# Misc.net
KiCad netlist of a schematic drawn in Altium Designer
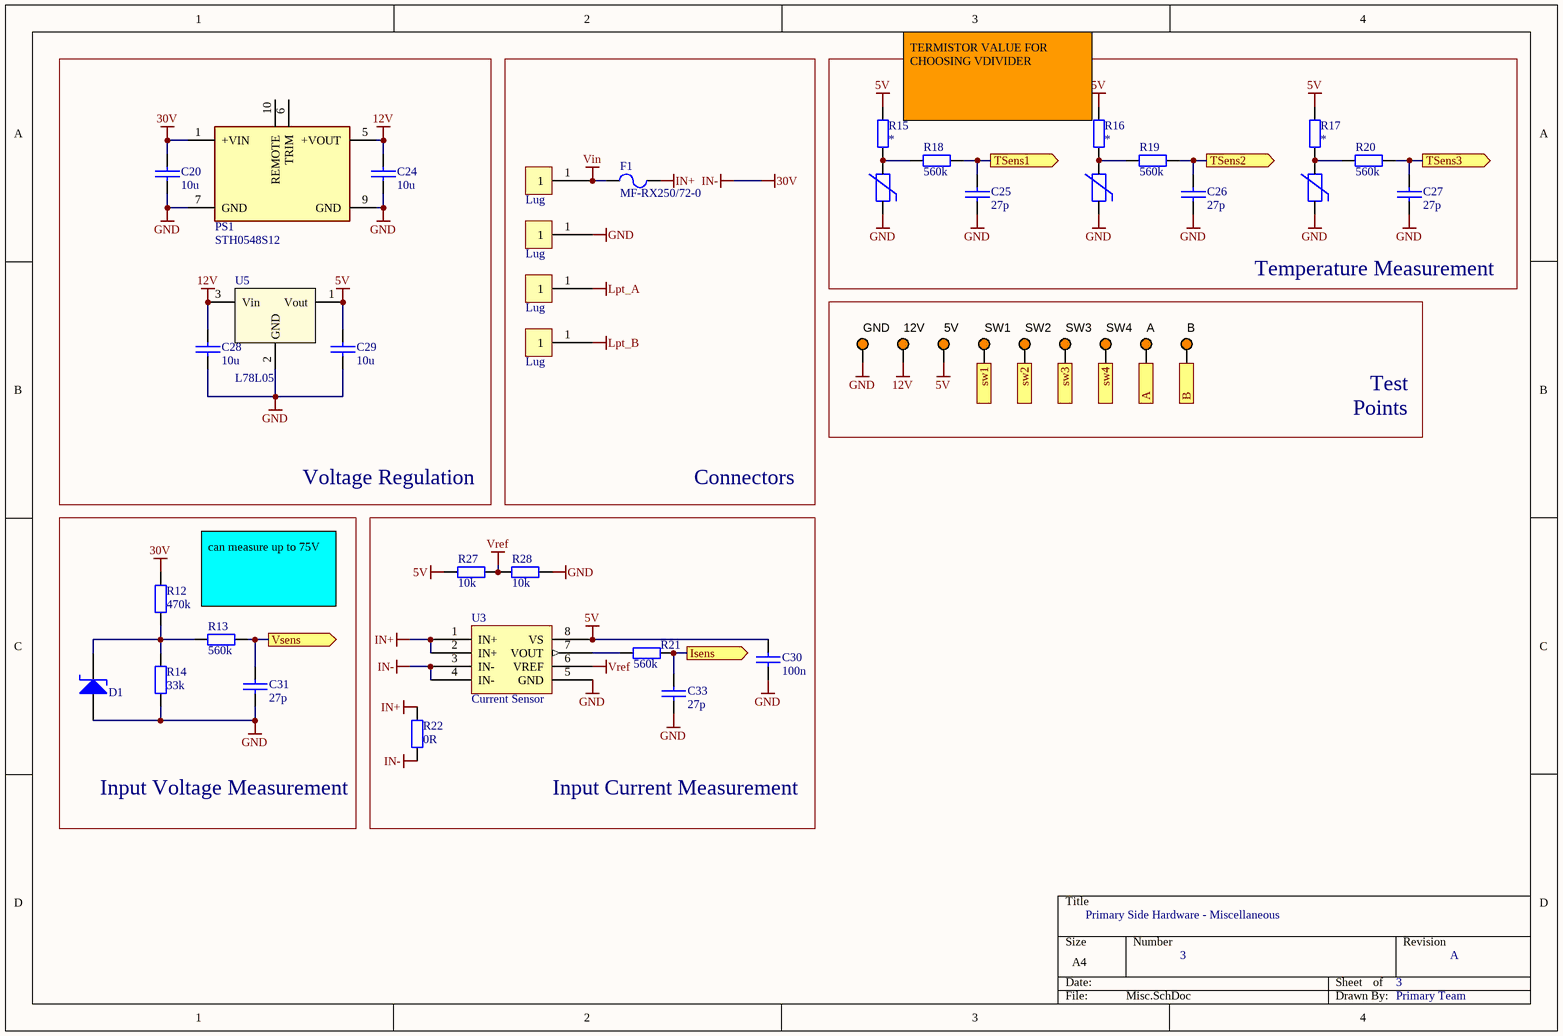
[diagram p0: Misc.SchDoc]

(export (version "E")
  (design (tool "Eeschema 10.0.6"))
  (components
    (comp (ref "5V")
      (value "5003")
      (footprint "TP_TH")
      (description "Test Point, Orange, 1-Pin THD, RoHS")
      (libsource (lib "Workshop_Library") (part "TestPoint"))
    )
    (comp (ref "12V")
      (value "5003")
      (footprint "TP_TH")
      (description "Test Point, Orange, 1-Pin THD, RoHS")
      (libsource (lib "Workshop_Library") (part "TestPoint"))
    )
    (comp (ref "A")
      (value "5003")
      (footprint "TP_TH")
      (description "Test Point, Orange, 1-Pin THD, RoHS")
      (libsource (lib "Workshop_Library") (part "TestPoint"))
    )
    (comp (ref "B")
      (value "5003")
      (footprint "TP_TH")
      (description "Test Point, Orange, 1-Pin THD, RoHS")
      (libsource (lib "Workshop_Library") (part "TestPoint"))
    )
    (comp (ref "C20")
      (value "10u")
      (footprint "C1210")
      (description "SMT ceramic capacitor selectable size")
      (libsource (lib "Workshop_Library") (part "CerCap_SMT"))
    )
    (comp (ref "C24")
      (value "10u")
      (footprint "C1210")
      (description "SMT ceramic capacitor selectable size")
      (libsource (lib "Workshop_Library") (part "CerCap_SMT"))
    )
    (comp (ref "C25")
      (value "27p")
      (footprint "C0805")
      (description "SMT ceramic capacitor selectable size")
      (libsource (lib "Workshop_Library") (part "CerCap_SMT"))
    )
    (comp (ref "C26")
      (value "27p")
      (footprint "C0805")
      (description "SMT ceramic capacitor selectable size")
      (libsource (lib "Workshop_Library") (part "CerCap_SMT"))
    )
    (comp (ref "C27")
      (value "27p")
      (footprint "C0805")
      (description "SMT ceramic capacitor selectable size")
      (libsource (lib "Workshop_Library") (part "CerCap_SMT"))
    )
    (comp (ref "C28")
      (value "10u")
      (footprint "C1210")
      (description "SMT ceramic capacitor selectable size")
      (libsource (lib "Workshop_Library") (part "CerCap_SMT"))
    )
    (comp (ref "C29")
      (value "10u")
      (footprint "C1210")
      (description "SMT ceramic capacitor selectable size")
      (libsource (lib "Workshop_Library") (part "CerCap_SMT"))
    )
    (comp (ref "C30")
      (value "100n")
      (footprint "C0805")
      (description "SMT ceramic capacitor selectable size")
      (libsource (lib "Workshop_Library") (part "CerCap_SMT"))
    )
    (comp (ref "C31")
      (value "27p")
      (footprint "C0805")
      (description "SMT ceramic capacitor selectable size")
      (libsource (lib "Workshop_Library") (part "CerCap_SMT"))
    )
    (comp (ref "C33")
      (value "27p")
      (footprint "C0805")
      (description "SMT ceramic capacitor selectable size")
      (libsource (lib "Workshop_Library") (part "CerCap_SMT"))
    )
    (comp (ref "D1")
      (value "BZT52H-B5V1")
      (footprint "SOD123")
      (description "SMT zener diode with SOD123 package")
      (fields
        (field (name "MANUFACTURER") "Nexperia USA Inc.")
        (field (name "MANUFACTURER PART NUMBER") "BZT52H-B5V1,115")
      )
      (libsource (lib "Workshop_Library") (part "Zener_SMT_SOD123"))
    )
    (comp (ref "F1")
      (value "MF-RX250/72-0")
      (footprint "TH_FUSE")
      (fields (field (name "MANUFACTURER") "Bourns"))
      (libsource (lib "Workshop_Library") (part "MF-RX250/72-0"))
    )
    (comp (ref "GND")
      (value "5003")
      (footprint "TP_TH")
      (description "Test Point, Orange, 1-Pin THD, RoHS")
      (libsource (lib "Workshop_Library") (part "TestPoint"))
    )
    (comp (ref "P2") (value "Lug") (footprint "M3 Lug") (libsource (lib "Workshop_Library") (part "Lug")))
    (comp (ref "P3") (value "Lug") (footprint "M4 Lug") (libsource (lib "Workshop_Library") (part "Lug")))
    (comp (ref "P4") (value "Lug") (footprint "M4 Lug") (libsource (lib "Workshop_Library") (part "Lug")))
    (comp (ref "P5") (value "Lug") (footprint "M3 Lug") (libsource (lib "Workshop_Library") (part "Lug")))
    (comp (ref "PS1")
      (value "STH0548S12")
      (footprint "STH0548S12")
      (description "Power Supply")
      (fields (field (name "MANUFACTURER_PART_NUMBER") "STH0548S15"))
      (libsource (lib "Workshop_Library") (part "STH0548S12"))
    )
    (comp (ref "R12")
      (value "470k")
      (footprint "R0805")
      (description "0805 or 1206 resistor")
      (fields (field (name "PUBLISHER") "Altium Limited"))
      (libsource (lib "Workshop_Library") (part "Res_SMT"))
    )
    (comp (ref "R13")
      (value "560k")
      (footprint "R0805")
      (description "0805 or 1206 resistor")
      (fields (field (name "PUBLISHER") "Altium Limited"))
      (libsource (lib "") (part "Res_SMT_1"))
    )
    (comp (ref "R14")
      (value "33k")
      (footprint "R0805")
      (description "0805 or 1206 resistor")
      (fields (field (name "PUBLISHER") "Altium Limited"))
      (libsource (lib "Workshop_Library") (part "Res_SMT"))
    )
    (comp (ref "R15")
      (value "*")
      (footprint "R0805")
      (description "0805 or 1206 resistor")
      (fields (field (name "PUBLISHER") "Altium Limited"))
      (libsource (lib "Workshop_Library") (part "Res_SMT"))
    )
    (comp (ref "R16")
      (value "*")
      (footprint "R0805")
      (description "0805 or 1206 resistor")
      (fields (field (name "PUBLISHER") "Altium Limited"))
      (libsource (lib "Workshop_Library") (part "Res_SMT"))
    )
    (comp (ref "R17")
      (value "*")
      (footprint "R0805")
      (description "0805 or 1206 resistor")
      (fields (field (name "PUBLISHER") "Altium Limited"))
      (libsource (lib "Workshop_Library") (part "Res_SMT"))
    )
    (comp (ref "R18")
      (value "560k")
      (footprint "R0805")
      (description "0805 or 1206 resistor")
      (fields (field (name "PUBLISHER") "Altium Limited"))
      (libsource (lib "") (part "Res_SMT_1"))
    )
    (comp (ref "R19")
      (value "560k")
      (footprint "R0805")
      (description "0805 or 1206 resistor")
      (fields (field (name "PUBLISHER") "Altium Limited"))
      (libsource (lib "") (part "Res_SMT_1"))
    )
    (comp (ref "R20")
      (value "560k")
      (footprint "R0805")
      (description "0805 or 1206 resistor")
      (fields (field (name "PUBLISHER") "Altium Limited"))
      (libsource (lib "") (part "Res_SMT_1"))
    )
    (comp (ref "R21")
      (value "560k")
      (footprint "R0805")
      (description "0805 or 1206 resistor")
      (fields (field (name "PUBLISHER") "Altium Limited"))
      (libsource (lib "") (part "Res_SMT_1"))
    )
    (comp (ref "R22")
      (value "0R")
      (footprint "R0805")
      (description "0805 or 1206 resistor")
      (fields (field (name "PUBLISHER") "Altium Limited"))
      (libsource (lib "") (part "Res_SMT_3"))
    )
    (comp (ref "R27")
      (value "10k")
      (footprint "R0805")
      (description "Resistor 0805 or 1206")
      (fields (field (name "PUBLISHER") "Altium Limited"))
      (libsource (lib "") (part "Res_SMT_2"))
    )
    (comp (ref "R28")
      (value "10k")
      (footprint "R0805")
      (description "Resistor 0805 or 1206")
      (fields (field (name "PUBLISHER") "Altium Limited"))
      (libsource (lib "") (part "Res_SMT_2"))
    )
    (comp (ref "SW1")
      (value "5003")
      (footprint "TP_TH")
      (description "Test Point, Orange, 1-Pin THD, RoHS")
      (libsource (lib "Workshop_Library") (part "TestPoint"))
    )
    (comp (ref "SW2")
      (value "5003")
      (footprint "TP_TH")
      (description "Test Point, Orange, 1-Pin THD, RoHS")
      (libsource (lib "Workshop_Library") (part "TestPoint"))
    )
    (comp (ref "SW3")
      (value "5003")
      (footprint "TP_TH")
      (description "Test Point, Orange, 1-Pin THD, RoHS")
      (libsource (lib "Workshop_Library") (part "TestPoint"))
    )
    (comp (ref "SW4")
      (value "5003")
      (footprint "TP_TH")
      (description "Test Point, Orange, 1-Pin THD, RoHS")
      (libsource (lib "Workshop_Library") (part "TestPoint"))
    )
    (comp (ref "T1")
      (value "Thermistor")
      (footprint "LeadedThermistor")
      (libsource (lib "SchLib") (part "Thermistor"))
    )
    (comp (ref "T2")
      (value "Thermistor")
      (footprint "LeadedThermistor")
      (libsource (lib "SchLib") (part "Thermistor"))
    )
    (comp (ref "T3")
      (value "Thermistor")
      (footprint "LeadedThermistor")
      (libsource (lib "SchLib") (part "Thermistor"))
    )
    (comp (ref "U3")
      (value "Current Sensor")
      (footprint "I-SOIC8")
      (description "TMCS1100")
      (libsource (lib "Workshop_Library") (part "Current Sensor"))
    )
    (comp (ref "U5")
      (value "L78L05")
      (footprint "SOT-89")
      (description "LDO Voltage Regulator 5V")
      (libsource (lib "Workshop_Library") (part "L78L05_SMT_SOT89"))
    )
  )
  (nets
    (net (code "1") (name "/A") (class "Default")
      (node (ref "A") (pin "1") (pinfunction "1_1") (pintype "passive"))
    )
    (net (code "2") (name "/B") (class "Default")
      (node (ref "B") (pin "1") (pinfunction "1_1") (pintype "passive"))
    )
    (net (code "3") (name "/Isens") (class "Default")
      (node (ref "C33") (pin "1") (pinfunction "1_1") (pintype "passive"))
      (node (ref "R21") (pin "1") (pinfunction "1_1") (pintype "passive"))
    )
    (net (code "4") (name "/TSens1") (class "Default")
      (node (ref "C25") (pin "1") (pinfunction "1_1") (pintype "passive"))
      (node (ref "R18") (pin "1") (pinfunction "1_1") (pintype "passive"))
    )
    (net (code "5") (name "/TSens2") (class "Default")
      (node (ref "C26") (pin "1") (pinfunction "1_1") (pintype "passive"))
      (node (ref "R19") (pin "1") (pinfunction "1_1") (pintype "passive"))
    )
    (net (code "6") (name "/TSens3") (class "Default")
      (node (ref "C27") (pin "1") (pinfunction "1_1") (pintype "passive"))
      (node (ref "R20") (pin "1") (pinfunction "1_1") (pintype "passive"))
    )
    (net (code "7") (name "/Vsens") (class "Default")
      (node (ref "C31") (pin "1") (pinfunction "1_1") (pintype "passive"))
      (node (ref "R13") (pin "1") (pinfunction "1_1") (pintype "passive"))
    )
    (net (code "8") (name "/sw1") (class "Default")
      (node (ref "SW1") (pin "1") (pinfunction "1_1") (pintype "passive"))
    )
    (net (code "9") (name "/sw2") (class "Default")
      (node (ref "SW2") (pin "1") (pinfunction "1_1") (pintype "passive"))
    )
    (net (code "10") (name "/sw3") (class "Default")
      (node (ref "SW3") (pin "1") (pinfunction "1_1") (pintype "passive"))
    )
    (net (code "11") (name "/sw4") (class "Default")
      (node (ref "SW4") (pin "1") (pinfunction "1_1") (pintype "passive"))
    )
    (net (code "12") (name "5V") (class "Default")
      (node (ref "5V") (pin "1") (pinfunction "1_1") (pintype "passive"))
      (node (ref "C29") (pin "1") (pinfunction "1_1") (pintype "passive"))
      (node (ref "C30") (pin "1") (pinfunction "1_1") (pintype "passive"))
      (node (ref "R15") (pin "2") (pinfunction "2_2") (pintype "passive"))
      (node (ref "R16") (pin "2") (pinfunction "2_2") (pintype "passive"))
      (node (ref "R17") (pin "2") (pinfunction "2_2") (pintype "passive"))
      (node (ref "R27") (pin "1") (pinfunction "1_1") (pintype "passive"))
      (node (ref "U3") (pin "8") (pinfunction "VS_8") (pintype "power_in"))
      (node (ref "U5") (pin "1") (pinfunction "Vout_1") (pintype "passive"))
    )
    (net (code "13") (name "12V") (class "Default")
      (node (ref "12V") (pin "1") (pinfunction "1_1") (pintype "passive"))
      (node (ref "C24") (pin "1") (pinfunction "1_1") (pintype "passive"))
      (node (ref "C28") (pin "1") (pinfunction "1_1") (pintype "passive"))
      (node (ref "PS1") (pin "5") (pinfunction "+VOUT_5") (pintype "passive"))
      (node (ref "U5") (pin "3") (pinfunction "Vin_3") (pintype "passive"))
    )
    (net (code "14") (name "30V") (class "Default")
      (node (ref "C20") (pin "1") (pinfunction "1_1") (pintype "passive"))
      (node (ref "PS1") (pin "1") (pinfunction "+VIN_1") (pintype "passive"))
      (node (ref "R12") (pin "2") (pinfunction "2_2") (pintype "passive"))
      (node (ref "R22") (pin "2") (pinfunction "2_2") (pintype "passive"))
      (node (ref "U3") (pin "3") (pinfunction "IN-_3") (pintype "power_in"))
      (node (ref "U3") (pin "4") (pinfunction "IN-_4") (pintype "power_in"))
    )
    (net (code "15") (name "GND") (class "Default")
      (node (ref "C20") (pin "2") (pinfunction "2_2") (pintype "passive"))
      (node (ref "C24") (pin "2") (pinfunction "2_2") (pintype "passive"))
      (node (ref "C25") (pin "2") (pinfunction "2_2") (pintype "passive"))
      (node (ref "C26") (pin "2") (pinfunction "2_2") (pintype "passive"))
      (node (ref "C27") (pin "2") (pinfunction "2_2") (pintype "passive"))
      (node (ref "C28") (pin "2") (pinfunction "2_2") (pintype "passive"))
      (node (ref "C29") (pin "2") (pinfunction "2_2") (pintype "passive"))
      (node (ref "C30") (pin "2") (pinfunction "2_2") (pintype "passive"))
      (node (ref "C31") (pin "2") (pinfunction "2_2") (pintype "passive"))
      (node (ref "C33") (pin "2") (pinfunction "2_2") (pintype "passive"))
      (node (ref "D1") (pin "1") (pinfunction "A_1") (pintype "passive"))
      (node (ref "GND") (pin "1") (pinfunction "1_1") (pintype "passive"))
      (node (ref "P5") (pin "1") (pinfunction "1_1") (pintype "passive"))
      (node (ref "PS1") (pin "7") (pinfunction "GND_7") (pintype "passive"))
      (node (ref "PS1") (pin "9") (pinfunction "GND_9") (pintype "passive"))
      (node (ref "R14") (pin "1") (pinfunction "1_1") (pintype "passive"))
      (node (ref "R28") (pin "2") (pinfunction "2_2") (pintype "passive"))
      (node (ref "T1") (pin "1") (pinfunction "1_1") (pintype "passive"))
      (node (ref "T2") (pin "1") (pinfunction "1_1") (pintype "passive"))
      (node (ref "T3") (pin "1") (pinfunction "1_1") (pintype "passive"))
      (node (ref "U3") (pin "5") (pinfunction "GND_5") (pintype "power_in"))
      (node (ref "U5") (pin "2") (pinfunction "GND_2") (pintype "passive"))
    )
    (net (code "16") (name "IN+") (class "Default")
      (node (ref "F1") (pin "2") (pinfunction "2_2") (pintype "passive"))
      (node (ref "R22") (pin "1") (pinfunction "1_1") (pintype "passive"))
      (node (ref "U3") (pin "1") (pinfunction "IN+_1") (pintype "power_in"))
      (node (ref "U3") (pin "2") (pinfunction "IN+_2") (pintype "power_in"))
    )
    (net (code "17") (name "Lpt_A") (class "Default")
      (node (ref "P3") (pin "1") (pinfunction "1_1") (pintype "passive"))
    )
    (net (code "18") (name "Lpt_B") (class "Default")
      (node (ref "P4") (pin "1") (pinfunction "1_1") (pintype "passive"))
    )
    (net (code "19") (name "Net-(D1-K)") (class "Default")
      (node (ref "D1") (pin "2") (pinfunction "K_2") (pintype "passive"))
      (node (ref "R12") (pin "1") (pinfunction "1_1") (pintype "passive"))
      (node (ref "R13") (pin "2") (pinfunction "2_2") (pintype "passive"))
      (node (ref "R14") (pin "2") (pinfunction "2_2") (pintype "passive"))
    )
    (net (code "20") (name "Net-(R15-Pad1)") (class "Default")
      (node (ref "R15") (pin "1") (pinfunction "1_1") (pintype "passive"))
      (node (ref "R18") (pin "2") (pinfunction "2_2") (pintype "passive"))
      (node (ref "T1") (pin "2") (pinfunction "2_2") (pintype "passive"))
    )
    (net (code "21") (name "Net-(R16-Pad1)") (class "Default")
      (node (ref "R16") (pin "1") (pinfunction "1_1") (pintype "passive"))
      (node (ref "R19") (pin "2") (pinfunction "2_2") (pintype "passive"))
      (node (ref "T2") (pin "2") (pinfunction "2_2") (pintype "passive"))
    )
    (net (code "22") (name "Net-(R17-Pad1)") (class "Default")
      (node (ref "R17") (pin "1") (pinfunction "1_1") (pintype "passive"))
      (node (ref "R20") (pin "2") (pinfunction "2_2") (pintype "passive"))
      (node (ref "T3") (pin "2") (pinfunction "2_2") (pintype "passive"))
    )
    (net (code "23") (name "Net-(U3-VOUT)") (class "Default")
      (node (ref "R21") (pin "2") (pinfunction "2_2") (pintype "passive"))
      (node (ref "U3") (pin "7") (pinfunction "VOUT_7") (pintype "output"))
    )
    (net (code "24") (name "Vin") (class "Default")
      (node (ref "F1") (pin "1") (pinfunction "1_1") (pintype "passive"))
      (node (ref "P2") (pin "1") (pinfunction "1_1") (pintype "passive"))
    )
    (net (code "25") (name "Vref") (class "Default")
      (node (ref "R27") (pin "2") (pinfunction "2_2") (pintype "passive"))
      (node (ref "R28") (pin "1") (pinfunction "1_1") (pintype "passive"))
      (node (ref "U3") (pin "6") (pinfunction "VREF_6") (pintype "power_in"))
    )
    (net (code "26") (name "unconnected-(PS1-REMOTE-Pad10)") (class "Default")
      (node (ref "PS1") (pin "10") (pinfunction "REMOTE_10") (pintype "passive"))
    )
    (net (code "27") (name "unconnected-(PS1-TRIM-Pad6)") (class "Default")
      (node (ref "PS1") (pin "6") (pinfunction "TRIM_6") (pintype "passive"))
    )
  )
)
